# v2.net
KiCad netlist of a schematic drawn in Altium Designer
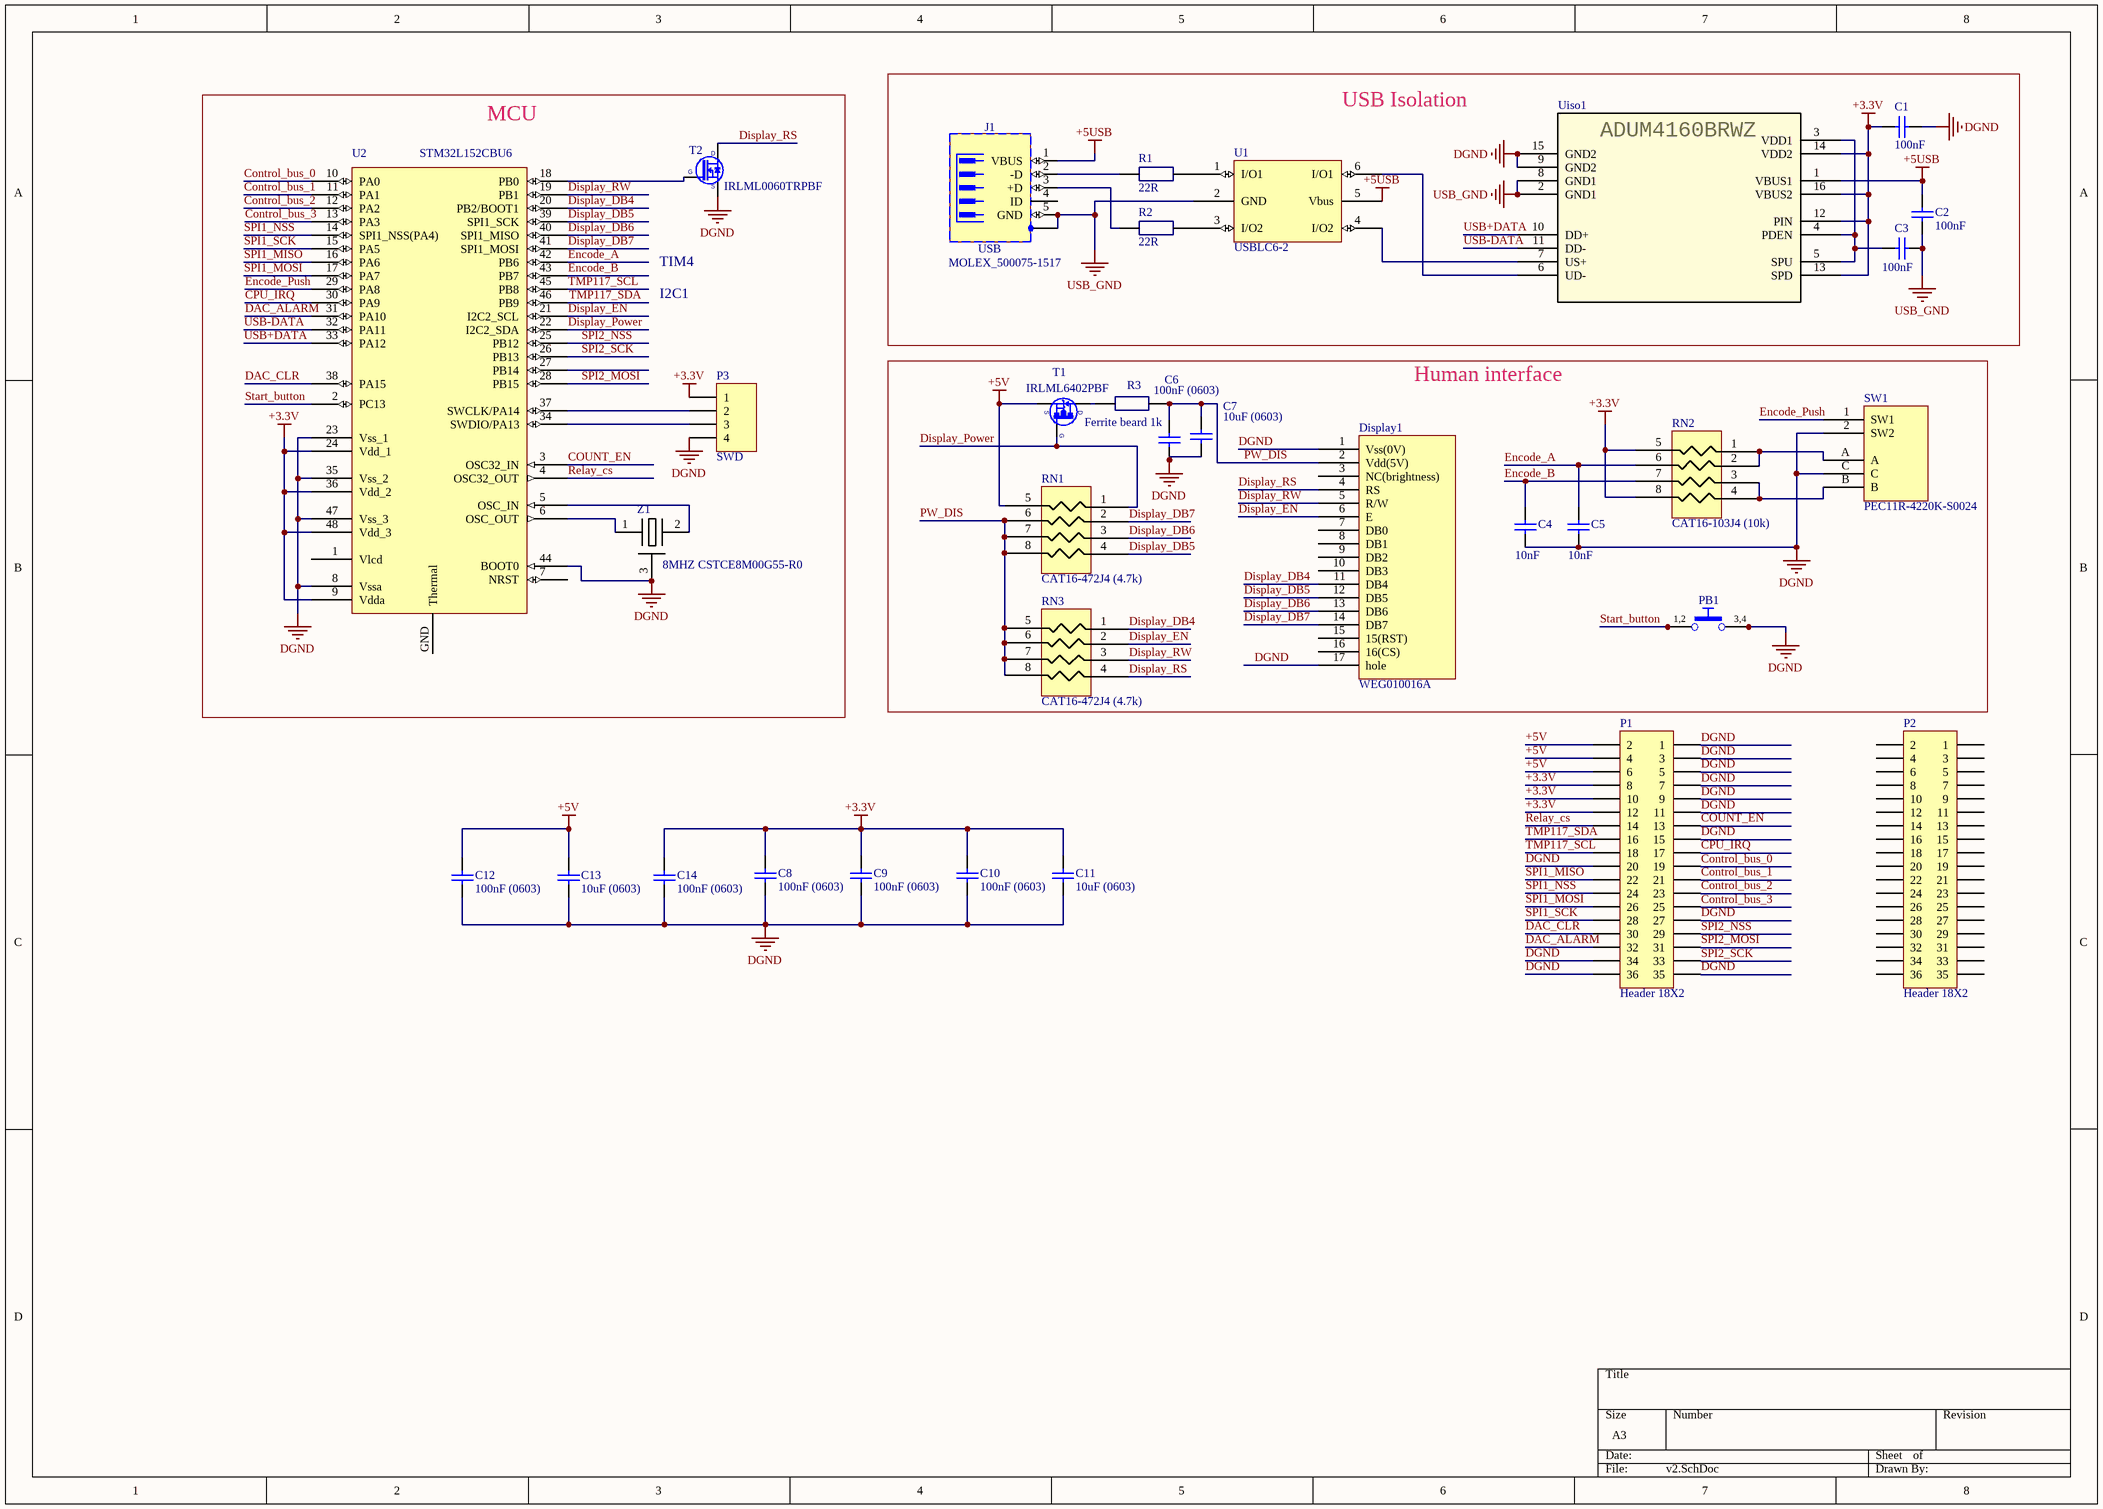
[diagram p0: v2.SchDoc]

(export (version "E")
  (design (tool "Eeschema 10.0.6"))
  (components
    (comp (ref "C1")
      (value "100nF")
      (footprint "CAP 0603")
      (description "Capacitor (Semiconductor SIM Model)")
      (fields (field (name "PUBLISHER") "Altium Limited"))
      (libsource (lib "Miscellaneous Devices") (part "Cap Semi"))
    )
    (comp (ref "C2")
      (value "100nF")
      (footprint "CAP 0603")
      (description "Capacitor (Semiconductor SIM Model)")
      (fields (field (name "PUBLISHER") "Altium Limited"))
      (libsource (lib "Miscellaneous Devices") (part "Cap Semi"))
    )
    (comp (ref "C3")
      (value "100nF")
      (footprint "CAP 0603")
      (description "Capacitor (Semiconductor SIM Model)")
      (fields (field (name "PUBLISHER") "Altium Limited"))
      (libsource (lib "Miscellaneous Devices") (part "Cap Semi"))
    )
    (comp (ref "C4")
      (value "10nF")
      (footprint "CAP 0603")
      (description "Capacitor (Semiconductor SIM Model)")
      (fields (field (name "PUBLISHER") "Altium Limited"))
      (libsource (lib "Miscellaneous Devices") (part "Cap Semi"))
    )
    (comp (ref "C5")
      (value "10nF")
      (footprint "CAP 0603")
      (description "Capacitor (Semiconductor SIM Model)")
      (fields (field (name "PUBLISHER") "Altium Limited"))
      (libsource (lib "Miscellaneous Devices") (part "Cap Semi"))
    )
    (comp (ref "C6")
      (value "100nF (0603)")
      (footprint "CAP 0603")
      (description "Capacitor (Semiconductor SIM Model)")
      (fields (field (name "PUBLISHER") "Altium Limited"))
      (libsource (lib "Miscellaneous Devices") (part "Cap Semi"))
    )
    (comp (ref "C7")
      (value "10uF (0603)")
      (footprint "CAP 0603")
      (description "Capacitor (Semiconductor SIM Model)")
      (fields (field (name "PUBLISHER") "Altium Limited"))
      (libsource (lib "Miscellaneous Devices") (part "Cap Semi"))
    )
    (comp (ref "C8")
      (value "100nF (0603)")
      (footprint "CAP 0603")
      (description "Capacitor (Semiconductor SIM Model)")
      (fields (field (name "PUBLISHER") "Altium Limited"))
      (libsource (lib "Miscellaneous Devices") (part "Cap Semi"))
    )
    (comp (ref "C9")
      (value "100nF (0603)")
      (footprint "CAP 0603")
      (description "Capacitor (Semiconductor SIM Model)")
      (fields (field (name "PUBLISHER") "Altium Limited"))
      (libsource (lib "Miscellaneous Devices") (part "Cap Semi"))
    )
    (comp (ref "C10")
      (value "100nF (0603)")
      (footprint "CAP 0603")
      (description "Capacitor (Semiconductor SIM Model)")
      (fields (field (name "PUBLISHER") "Altium Limited"))
      (libsource (lib "Miscellaneous Devices") (part "Cap Semi"))
    )
    (comp (ref "C11")
      (value "10uF (0603)")
      (footprint "CAP 0603")
      (description "Capacitor (Semiconductor SIM Model)")
      (fields (field (name "PUBLISHER") "Altium Limited"))
      (libsource (lib "Miscellaneous Devices") (part "Cap Semi"))
    )
    (comp (ref "C12")
      (value "100nF (0603)")
      (footprint "CAP 0603")
      (description "Capacitor (Semiconductor SIM Model)")
      (fields (field (name "PUBLISHER") "Altium Limited"))
      (libsource (lib "Miscellaneous Devices") (part "Cap Semi"))
    )
    (comp (ref "C13")
      (value "10uF (0603)")
      (footprint "CAP 0603")
      (description "Capacitor (Semiconductor SIM Model)")
      (fields (field (name "PUBLISHER") "Altium Limited"))
      (libsource (lib "Miscellaneous Devices") (part "Cap Semi"))
    )
    (comp (ref "C14")
      (value "100nF (0603)")
      (footprint "CAP 0603")
      (description "Capacitor (Semiconductor SIM Model)")
      (fields (field (name "PUBLISHER") "Altium Limited"))
      (libsource (lib "Miscellaneous Devices") (part "Cap Semi"))
    )
    (comp (ref "Display1")
      (value "WEG010016A")
      (footprint "WEG010016A")
      (libsource (lib "My SCH library") (part "WEG010016A"))
    )
    (comp (ref "J1")
      (value "USB")
      (footprint "MOLEX_500075-1517")
      (description "5 Pin + 1 Shield USB Receptacle")
      (fields
        (field (name "PART NUMBER") "MOLEX_500075-1517")
        (field (name "MANUFACTURER") "MOLEX")
        (field (name "MANUFACTURER PART NUMBER") "500075-1517")
        (field (name "AUTHOR") "CERN DEM JLC")
      )
      (libsource (lib "Connectors") (part "Connector USB 5 Pin + 1Shield"))
    )
    (comp (ref "P1")
      (value "Header 18X2")
      (footprint "HDR2X18")
      (description "Header, 18-Pin, Dual row")
      (fields (field (name "PUBLISHER") "Altium Limited"))
      (libsource (lib "Miscellaneous Connectors") (part "Header 18X2"))
    )
    (comp (ref "P2")
      (value "Header 18X2")
      (footprint "HDR2X18")
      (description "Header, 18-Pin, Dual row")
      (fields (field (name "PUBLISHER") "Altium Limited"))
      (libsource (lib "Miscellaneous Connectors") (part "Header 18X2"))
    )
    (comp (ref "P3")
      (value "SWD")
      (footprint "HDR1X4")
      (description "Header, 4-Pin")
      (fields (field (name "PUBLISHER") "Altium Limited"))
      (libsource (lib "Miscellaneous Connectors") (part "Header 4"))
    )
    (comp (ref "PB1")
      (value "Push Button")
      (footprint "PB_OMRON_B3F-1070")
      (description "Push-Button Switch SPDT")
      (fields
        (field (name "PART NUMBER") "PB_OMRON_B3F-1070")
        (field (name "MANUFACTURER") "OMRON")
        (field (name "AUTHOR") "CERN DEM JLC")
      )
      (libsource (lib "Eletro-mechanical") (part "PB SPST 12NO-34NO"))
    )
    (comp (ref "R1")
      (value "22R")
      (footprint "1608[0603]")
      (libsource (lib "Микрон-3") (part "Resistor 0805"))
    )
    (comp (ref "R2")
      (value "22R")
      (footprint "1608[0603]")
      (libsource (lib "Микрон-3") (part "Resistor 0805"))
    )
    (comp (ref "R3")
      (value "Ferrite beard 1k")
      (footprint "C1206")
      (libsource (lib "Микрон-3") (part "Resistor 0805"))
    )
    (comp (ref "RN1")
      (value "CAT16-472J4 (4.7k)")
      (footprint "CAT16-470J4LF")
      (libsource (lib "My SCH library") (part "CAT16-470J4LF"))
    )
    (comp (ref "RN2")
      (value "CAT16-103J4 (10k)")
      (footprint "CAT16-470J4LF")
      (libsource (lib "My SCH library") (part "CAT16-470J4LF"))
    )
    (comp (ref "RN3")
      (value "CAT16-472J4 (4.7k)")
      (footprint "CAT16-470J4LF")
      (libsource (lib "My SCH library") (part "CAT16-470J4LF"))
    )
    (comp (ref "SW1")
      (value "PEC11R-4220K-S0024")
      (footprint "PEC11R-4220K-S0024")
      (libsource (lib "My SCH library") (part "PEC11R-4220K-S0024"))
    )
    (comp (ref "T1")
      (value "IRLML6402PBF")
      (footprint "SOT95P237X112-3N")
      (description "P-CHANNEL MOSFET WITH ZENER DIODE")
      (fields (field (name "MANUFACTURER") "INTERNATIONAL RECTIFIER") (field (name "AUTHOR") "CERN DEM JLC"))
      (libsource (lib "ICs And Semiconductors") (part "P-MOSFET-DZ 1G 2S 3D"))
    )
    (comp (ref "T2")
      (value "IRLML0060TRPBF")
      (footprint "SOT95P237X112-3N")
      (description "N-CHANNEL MOSFET WITH DIODE")
      (fields (field (name "MANUFACTURER") "INTERNATIONAL RECTIFIER") (field (name "AUTHOR") "CERN DEM JLC"))
      (libsource (lib "ICs And Semiconductors") (part "N-MOSFET-D 1G 2S 3D"))
    )
    (comp (ref "U1") (value "USBLC6-2") (footprint "SOT23-6L") (libsource (lib "Микрон-3") (part "USBLC6-2")))
    (comp (ref "U2")
      (value "STM32L152CBU6")
      (footprint "UFQFPN48")
      (libsource (lib "My SCH library") (part "STM32L152CBU6"))
    )
    (comp (ref "Uiso1")
      (value "~")
      (footprint "RW_16_ADI")
      (description "No Description Available")
      (fields
        (field (name "MANUFACTURER_PART_NUMBER") "ADUM4160BRWZ")
        (field (name "COPYRIGHT") "Copyright (C) 2018 Accelerated Designs. All rights reserved")
      )
      (libsource (lib "Ramp-generator") (part "ADUM4160BRWZ"))
    )
    (comp (ref "Z1")
      (value "8MHZ CSTCE8M00G55-R0")
      (footprint "PRQV8.00CR5010Y000")
      (libsource (lib "My SCH library") (part "8MHZ_cap"))
    )
  )
  (nets
    (net (code "1") (name "+3.3V") (class "Default")
      (node (ref "C1") (pin "2") (pinfunction "2_2") (pintype "passive"))
      (node (ref "C10") (pin "1") (pinfunction "1_1") (pintype "passive"))
      (node (ref "C11") (pin "1") (pinfunction "1_1") (pintype "passive"))
      (node (ref "C14") (pin "1") (pinfunction "1_1") (pintype "passive"))
      (node (ref "C8") (pin "1") (pinfunction "1_1") (pintype "passive"))
      (node (ref "C9") (pin "1") (pinfunction "1_1") (pintype "passive"))
      (node (ref "P1") (pin "10") (pinfunction "10_10") (pintype "passive"))
      (node (ref "P1") (pin "12") (pinfunction "12_12") (pintype "passive"))
      (node (ref "P1") (pin "8") (pinfunction "8_8") (pintype "passive"))
      (node (ref "P3") (pin "1") (pinfunction "1_1") (pintype "passive"))
      (node (ref "RN2") (pin "5") (pinfunction "5_5") (pintype "passive"))
      (node (ref "RN2") (pin "8") (pinfunction "8_8") (pintype "passive"))
      (node (ref "U2") (pin "24") (pinfunction "Vdd_1_24") (pintype "power_in"))
      (node (ref "U2") (pin "36") (pinfunction "Vdd_2_36") (pintype "power_in"))
      (node (ref "U2") (pin "48") (pinfunction "Vdd_3_48") (pintype "power_in"))
      (node (ref "U2") (pin "9") (pinfunction "Vdda_9") (pintype "power_in"))
      (node (ref "Uiso1") (pin "12") (pinfunction "PIN_12") (pintype "passive"))
      (node (ref "Uiso1") (pin "13") (pinfunction "SPD_13") (pintype "passive"))
      (node (ref "Uiso1") (pin "14") (pinfunction "VDD2_14") (pintype "passive"))
      (node (ref "Uiso1") (pin "16") (pinfunction "VBUS2_16") (pintype "passive"))
    )
    (net (code "2") (name "+5USB") (class "Default")
      (node (ref "C2") (pin "2") (pinfunction "2_2") (pintype "passive"))
      (node (ref "J1") (pin "1") (pinfunction "VBUS_1") (pintype "bidirectional"))
      (node (ref "U1") (pin "5") (pinfunction "Vbus_5") (pintype "power_in"))
      (node (ref "Uiso1") (pin "1") (pinfunction "VBUS1_1") (pintype "passive"))
    )
    (net (code "3") (name "+5V") (class "Default")
      (node (ref "C12") (pin "1") (pinfunction "1_1") (pintype "passive"))
      (node (ref "C13") (pin "1") (pinfunction "1_1") (pintype "passive"))
      (node (ref "P1") (pin "2") (pinfunction "2_2") (pintype "passive"))
      (node (ref "P1") (pin "4") (pinfunction "4_4") (pintype "passive"))
      (node (ref "P1") (pin "6") (pinfunction "6_6") (pintype "passive"))
      (node (ref "RN1") (pin "5") (pinfunction "5_5") (pintype "passive"))
      (node (ref "T1") (pin "2") (pinfunction "S_2") (pintype "passive"))
    )
    (net (code "4") (name "/COUNT_EN") (class "Default")
      (node (ref "P1") (pin "13") (pinfunction "13_13") (pintype "passive"))
      (node (ref "U2") (pin "3") (pinfunction "OSC32_IN_3") (pintype "input"))
    )
    (net (code "5") (name "/CPU_IRQ") (class "Default")
      (node (ref "P1") (pin "17") (pinfunction "17_17") (pintype "passive"))
      (node (ref "U2") (pin "30") (pinfunction "PA9_30") (pintype "bidirectional"))
    )
    (net (code "6") (name "/Control_bus_0") (class "Default")
      (node (ref "P1") (pin "19") (pinfunction "19_19") (pintype "passive"))
      (node (ref "U2") (pin "10") (pinfunction "PA0_10") (pintype "bidirectional"))
    )
    (net (code "7") (name "/Control_bus_1") (class "Default")
      (node (ref "P1") (pin "21") (pinfunction "21_21") (pintype "passive"))
      (node (ref "U2") (pin "11") (pinfunction "PA1_11") (pintype "bidirectional"))
    )
    (net (code "8") (name "/Control_bus_2") (class "Default")
      (node (ref "P1") (pin "23") (pinfunction "23_23") (pintype "passive"))
      (node (ref "U2") (pin "12") (pinfunction "PA2_12") (pintype "bidirectional"))
    )
    (net (code "9") (name "/Control_bus_3") (class "Default")
      (node (ref "P1") (pin "25") (pinfunction "25_25") (pintype "passive"))
      (node (ref "U2") (pin "13") (pinfunction "PA3_13") (pintype "bidirectional"))
    )
    (net (code "10") (name "/DAC_ALARM") (class "Default")
      (node (ref "P1") (pin "32") (pinfunction "32_32") (pintype "passive"))
      (node (ref "U2") (pin "31") (pinfunction "PA10_31") (pintype "bidirectional"))
    )
    (net (code "11") (name "/DAC_CLR") (class "Default")
      (node (ref "P1") (pin "30") (pinfunction "30_30") (pintype "passive"))
      (node (ref "U2") (pin "38") (pinfunction "PA15_38") (pintype "bidirectional"))
    )
    (net (code "12") (name "/Display_DB4") (class "Default")
      (node (ref "Display1") (pin "11") (pinfunction "DB4_11") (pintype "passive"))
      (node (ref "RN3") (pin "1") (pinfunction "1_1") (pintype "passive"))
      (node (ref "U2") (pin "20") (pinfunction "PB2/BOOT1_20") (pintype "bidirectional"))
    )
    (net (code "13") (name "/Display_DB5") (class "Default")
      (node (ref "Display1") (pin "12") (pinfunction "DB5_12") (pintype "passive"))
      (node (ref "RN1") (pin "4") (pinfunction "4_4") (pintype "passive"))
      (node (ref "U2") (pin "39") (pinfunction "SPI1_SCK_39") (pintype "bidirectional"))
    )
    (net (code "14") (name "/Display_DB6") (class "Default")
      (node (ref "Display1") (pin "13") (pinfunction "DB6_13") (pintype "passive"))
      (node (ref "RN1") (pin "3") (pinfunction "3_3") (pintype "passive"))
      (node (ref "U2") (pin "40") (pinfunction "SPI1_MISO_40") (pintype "bidirectional"))
    )
    (net (code "15") (name "/Display_DB7") (class "Default")
      (node (ref "Display1") (pin "14") (pinfunction "DB7_14") (pintype "passive"))
      (node (ref "RN1") (pin "2") (pinfunction "2_2") (pintype "passive"))
      (node (ref "U2") (pin "41") (pinfunction "SPI1_MOSI_41") (pintype "bidirectional"))
    )
    (net (code "16") (name "/Display_EN") (class "Default")
      (node (ref "Display1") (pin "6") (pinfunction "E_6") (pintype "passive"))
      (node (ref "RN3") (pin "2") (pinfunction "2_2") (pintype "passive"))
      (node (ref "U2") (pin "21") (pinfunction "I2C2_SCL_21") (pintype "bidirectional"))
    )
    (net (code "17") (name "/Display_Power") (class "Default")
      (node (ref "RN1") (pin "1") (pinfunction "1_1") (pintype "passive"))
      (node (ref "T1") (pin "1") (pinfunction "G_1") (pintype "passive"))
      (node (ref "U2") (pin "22") (pinfunction "I2C2_SDA_22") (pintype "bidirectional"))
    )
    (net (code "18") (name "/Display_RS") (class "Default")
      (node (ref "Display1") (pin "4") (pinfunction "RS_4") (pintype "passive"))
      (node (ref "RN3") (pin "4") (pinfunction "4_4") (pintype "passive"))
      (node (ref "T2") (pin "3") (pinfunction "D_3") (pintype "passive"))
    )
    (net (code "19") (name "/Display_RW") (class "Default")
      (node (ref "Display1") (pin "5") (pinfunction "R/W_5") (pintype "passive"))
      (node (ref "RN3") (pin "3") (pinfunction "3_3") (pintype "passive"))
      (node (ref "U2") (pin "19") (pinfunction "PB1_19") (pintype "bidirectional"))
    )
    (net (code "20") (name "/Encode_A") (class "Default")
      (node (ref "C5") (pin "1") (pinfunction "1_1") (pintype "passive"))
      (node (ref "RN2") (pin "6") (pinfunction "6_6") (pintype "passive"))
      (node (ref "U2") (pin "42") (pinfunction "PB6_42") (pintype "bidirectional"))
    )
    (net (code "21") (name "/Encode_B") (class "Default")
      (node (ref "C4") (pin "1") (pinfunction "1_1") (pintype "passive"))
      (node (ref "RN2") (pin "7") (pinfunction "7_7") (pintype "passive"))
      (node (ref "U2") (pin "43") (pinfunction "PB7_43") (pintype "bidirectional"))
    )
    (net (code "22") (name "/Encode_Push") (class "Default")
      (node (ref "SW1") (pin "1") (pinfunction "SW1_1") (pintype "open_collector"))
      (node (ref "U2") (pin "29") (pinfunction "PA8_29") (pintype "bidirectional"))
    )
    (net (code "23") (name "/PW_DIS") (class "Default")
      (node (ref "C6") (pin "1") (pinfunction "1_1") (pintype "passive"))
      (node (ref "C7") (pin "1") (pinfunction "1_1") (pintype "passive"))
      (node (ref "Display1") (pin "2") (pinfunction "Vdd(5V)_2") (pintype "passive"))
      (node (ref "R3") (pin "1") (pinfunction "A_1") (pintype "passive"))
      (node (ref "RN1") (pin "6") (pinfunction "6_6") (pintype "passive"))
      (node (ref "RN1") (pin "7") (pinfunction "7_7") (pintype "passive"))
      (node (ref "RN1") (pin "8") (pinfunction "8_8") (pintype "passive"))
      (node (ref "RN3") (pin "5") (pinfunction "5_5") (pintype "passive"))
      (node (ref "RN3") (pin "6") (pinfunction "6_6") (pintype "passive"))
      (node (ref "RN3") (pin "7") (pinfunction "7_7") (pintype "passive"))
      (node (ref "RN3") (pin "8") (pinfunction "8_8") (pintype "passive"))
    )
    (net (code "24") (name "/Relay_cs") (class "Default")
      (node (ref "P1") (pin "14") (pinfunction "14_14") (pintype "passive"))
      (node (ref "U2") (pin "4") (pinfunction "OSC32_OUT_4") (pintype "output"))
    )
    (net (code "25") (name "/SPI1_MISO") (class "Default")
      (node (ref "P1") (pin "22") (pinfunction "22_22") (pintype "passive"))
      (node (ref "U2") (pin "16") (pinfunction "PA6_16") (pintype "bidirectional"))
    )
    (net (code "26") (name "/SPI1_MOSI") (class "Default")
      (node (ref "P1") (pin "26") (pinfunction "26_26") (pintype "passive"))
      (node (ref "U2") (pin "17") (pinfunction "PA7_17") (pintype "bidirectional"))
    )
    (net (code "27") (name "/SPI1_NSS") (class "Default")
      (node (ref "P1") (pin "24") (pinfunction "24_24") (pintype "passive"))
      (node (ref "U2") (pin "14") (pinfunction "SPI1_NSS(PA4)_14") (pintype "bidirectional"))
    )
    (net (code "28") (name "/SPI1_SCK") (class "Default")
      (node (ref "P1") (pin "28") (pinfunction "28_28") (pintype "passive"))
      (node (ref "U2") (pin "15") (pinfunction "PA5_15") (pintype "bidirectional"))
    )
    (net (code "29") (name "/SPI2_MOSI") (class "Default")
      (node (ref "P1") (pin "31") (pinfunction "31_31") (pintype "passive"))
      (node (ref "U2") (pin "28") (pinfunction "PB15_28") (pintype "bidirectional"))
    )
    (net (code "30") (name "/SPI2_NSS") (class "Default")
      (node (ref "P1") (pin "29") (pinfunction "29_29") (pintype "passive"))
      (node (ref "U2") (pin "25") (pinfunction "PB12_25") (pintype "bidirectional"))
    )
    (net (code "31") (name "/SPI2_SCK") (class "Default")
      (node (ref "P1") (pin "33") (pinfunction "33_33") (pintype "passive"))
      (node (ref "U2") (pin "26") (pinfunction "PB13_26") (pintype "bidirectional"))
    )
    (net (code "32") (name "/Start_button") (class "Default")
      (node (ref "PB1") (pin "1") (pinfunction "1_1") (pintype "passive"))
      (node (ref "PB1") (pin "2") (pinfunction "2_2") (pintype "passive"))
      (node (ref "U2") (pin "2") (pinfunction "PC13_2") (pintype "bidirectional"))
    )
    (net (code "33") (name "/TMP117_SCL") (class "Default")
      (node (ref "P1") (pin "18") (pinfunction "18_18") (pintype "passive"))
      (node (ref "U2") (pin "45") (pinfunction "PB8_45") (pintype "bidirectional"))
    )
    (net (code "34") (name "/TMP117_SDA") (class "Default")
      (node (ref "P1") (pin "16") (pinfunction "16_16") (pintype "passive"))
      (node (ref "U2") (pin "46") (pinfunction "PB9_46") (pintype "bidirectional"))
    )
    (net (code "35") (name "/USB+DATA") (class "Default")
      (node (ref "U2") (pin "33") (pinfunction "PA12_33") (pintype "bidirectional"))
      (node (ref "Uiso1") (pin "10") (pinfunction "DD+_10") (pintype "passive"))
    )
    (net (code "36") (name "/USB-DATA") (class "Default")
      (node (ref "U2") (pin "32") (pinfunction "PA11_32") (pintype "bidirectional"))
      (node (ref "Uiso1") (pin "11") (pinfunction "DD-_11") (pintype "passive"))
    )
    (net (code "37") (name "DGND") (class "Default")
      (node (ref "C1") (pin "1") (pinfunction "1_1") (pintype "passive"))
      (node (ref "C10") (pin "2") (pinfunction "2_2") (pintype "passive"))
      (node (ref "C11") (pin "2") (pinfunction "2_2") (pintype "passive"))
      (node (ref "C12") (pin "2") (pinfunction "2_2") (pintype "passive"))
      (node (ref "C13") (pin "2") (pinfunction "2_2") (pintype "passive"))
      (node (ref "C14") (pin "2") (pinfunction "2_2") (pintype "passive"))
      (node (ref "C4") (pin "2") (pinfunction "2_2") (pintype "passive"))
      (node (ref "C5") (pin "2") (pinfunction "2_2") (pintype "passive"))
      (node (ref "C6") (pin "2") (pinfunction "2_2") (pintype "passive"))
      (node (ref "C7") (pin "2") (pinfunction "2_2") (pintype "passive"))
      (node (ref "C8") (pin "2") (pinfunction "2_2") (pintype "passive"))
      (node (ref "C9") (pin "2") (pinfunction "2_2") (pintype "passive"))
      (node (ref "Display1") (pin "1") (pinfunction "Vss(0V)_1") (pintype "passive"))
      (node (ref "Display1") (pin "17") (pinfunction "hole_17") (pintype "passive"))
      (node (ref "P1") (pin "1") (pinfunction "1_1") (pintype "passive"))
      (node (ref "P1") (pin "11") (pinfunction "11_11") (pintype "passive"))
      (node (ref "P1") (pin "15") (pinfunction "15_15") (pintype "passive"))
      (node (ref "P1") (pin "20") (pinfunction "20_20") (pintype "passive"))
      (node (ref "P1") (pin "27") (pinfunction "27_27") (pintype "passive"))
      (node (ref "P1") (pin "3") (pinfunction "3_3") (pintype "passive"))
      (node (ref "P1") (pin "34") (pinfunction "34_34") (pintype "passive"))
      (node (ref "P1") (pin "35") (pinfunction "35_35") (pintype "passive"))
      (node (ref "P1") (pin "36") (pinfunction "36_36") (pintype "passive"))
      (node (ref "P1") (pin "5") (pinfunction "5_5") (pintype "passive"))
      (node (ref "P1") (pin "7") (pinfunction "7_7") (pintype "passive"))
      (node (ref "P1") (pin "9") (pinfunction "9_9") (pintype "passive"))
      (node (ref "P3") (pin "4") (pinfunction "4_4") (pintype "passive"))
      (node (ref "PB1") (pin "3") (pinfunction "3_3") (pintype "passive"))
      (node (ref "PB1") (pin "4") (pinfunction "4_4") (pintype "passive"))
      (node (ref "SW1") (pin "2") (pinfunction "SW2_2") (pintype "open_collector"))
      (node (ref "SW1") (pin "C") (pinfunction "C_C") (pintype "open_collector"))
      (node (ref "T2") (pin "2") (pinfunction "S_2") (pintype "passive"))
      (node (ref "U2") (pin "23") (pinfunction "Vss_1_23") (pintype "power_in"))
      (node (ref "U2") (pin "35") (pinfunction "Vss_2_35") (pintype "power_in"))
      (node (ref "U2") (pin "44") (pinfunction "BOOT0_44") (pintype "input"))
      (node (ref "U2") (pin "47") (pinfunction "Vss_3_47") (pintype "power_in"))
      (node (ref "U2") (pin "8") (pinfunction "Vssa_8") (pintype "power_in"))
      (node (ref "Uiso1") (pin "15") (pinfunction "GND2_15") (pintype "passive"))
      (node (ref "Uiso1") (pin "9") (pinfunction "GND2_9") (pintype "passive"))
      (node (ref "Z1") (pin "3") (pinfunction "50_3") (pintype "passive"))
    )
    (net (code "38") (name "Net-(J1-+D)") (class "Default")
      (node (ref "J1") (pin "3") (pinfunction "+D_3") (pintype "bidirectional"))
      (node (ref "R2") (pin "2") (pinfunction "2_2") (pintype "passive"))
    )
    (net (code "39") (name "Net-(J1--D)") (class "Default")
      (node (ref "J1") (pin "2") (pinfunction "-D_2") (pintype "bidirectional"))
      (node (ref "R1") (pin "2") (pinfunction "2_2") (pintype "passive"))
    )
    (net (code "40") (name "Net-(R1-A)") (class "Default")
      (node (ref "R1") (pin "1") (pinfunction "A_1") (pintype "passive"))
      (node (ref "U1") (pin "1") (pinfunction "I/O1_1") (pintype "bidirectional"))
    )
    (net (code "41") (name "Net-(R2-A)") (class "Default")
      (node (ref "R2") (pin "1") (pinfunction "A_1") (pintype "passive"))
      (node (ref "U1") (pin "3") (pinfunction "I/O2_3") (pintype "bidirectional"))
    )
    (net (code "42") (name "Net-(RN2-Pad1)") (class "Default")
      (node (ref "RN2") (pin "1") (pinfunction "1_1") (pintype "passive"))
      (node (ref "RN2") (pin "2") (pinfunction "2_2") (pintype "passive"))
      (node (ref "SW1") (pin "A") (pinfunction "A_A") (pintype "open_collector"))
    )
    (net (code "43") (name "Net-(RN2-Pad3)") (class "Default")
      (node (ref "RN2") (pin "3") (pinfunction "3_3") (pintype "passive"))
      (node (ref "RN2") (pin "4") (pinfunction "4_4") (pintype "passive"))
      (node (ref "SW1") (pin "B") (pinfunction "B_B") (pintype "open_collector"))
    )
    (net (code "44") (name "Net-(T1-D)") (class "Default")
      (node (ref "R3") (pin "2") (pinfunction "2_2") (pintype "passive"))
      (node (ref "T1") (pin "3") (pinfunction "D_3") (pintype "passive"))
    )
    (net (code "45") (name "Net-(T2-G)") (class "Default")
      (node (ref "T2") (pin "1") (pinfunction "G_1") (pintype "passive"))
      (node (ref "U2") (pin "18") (pinfunction "PB0_18") (pintype "bidirectional"))
    )
    (net (code "46") (name "Net-(U2-OSC_IN)") (class "Default")
      (node (ref "U2") (pin "5") (pinfunction "OSC_IN_5") (pintype "input"))
      (node (ref "Z1") (pin "2") (pinfunction "2_2") (pintype "passive"))
    )
    (net (code "47") (name "Net-(U2-OSC_OUT)") (class "Default")
      (node (ref "U2") (pin "6") (pinfunction "OSC_OUT_6") (pintype "output"))
      (node (ref "Z1") (pin "1") (pinfunction "50_1") (pintype "passive"))
    )
    (net (code "48") (name "Net-(U2-SWCLK{slash}PA14)") (class "Default")
      (node (ref "P3") (pin "2") (pinfunction "2_2") (pintype "passive"))
      (node (ref "U2") (pin "37") (pinfunction "SWCLK/PA14_37") (pintype "bidirectional"))
    )
    (net (code "49") (name "Net-(U2-SWDIO{slash}PA13)") (class "Default")
      (node (ref "P3") (pin "3") (pinfunction "3_3") (pintype "passive"))
      (node (ref "U2") (pin "34") (pinfunction "SWDIO/PA13_34") (pintype "bidirectional"))
    )
    (net (code "50") (name "Net-(Uiso1-PDEN)") (class "Default")
      (node (ref "C3") (pin "2") (pinfunction "2_2") (pintype "passive"))
      (node (ref "Uiso1") (pin "3") (pinfunction "VDD1_3") (pintype "passive"))
      (node (ref "Uiso1") (pin "4") (pinfunction "PDEN_4") (pintype "passive"))
      (node (ref "Uiso1") (pin "5") (pinfunction "SPU_5") (pintype "passive"))
    )
    (net (code "51") (name "Net-(Uiso1-UD-)") (class "Default")
      (node (ref "U1") (pin "6") (pinfunction "I/O1_6") (pintype "bidirectional"))
      (node (ref "Uiso1") (pin "6") (pinfunction "UD-_6") (pintype "passive"))
    )
    (net (code "52") (name "Net-(Uiso1-US+)") (class "Default")
      (node (ref "U1") (pin "4") (pinfunction "I/O2_4") (pintype "bidirectional"))
      (node (ref "Uiso1") (pin "7") (pinfunction "US+_7") (pintype "passive"))
    )
    (net (code "53") (name "USB_GND") (class "Default")
      (node (ref "C2") (pin "1") (pinfunction "1_1") (pintype "passive"))
      (node (ref "C3") (pin "1") (pinfunction "1_1") (pintype "passive"))
      (node (ref "J1") (pin "5") (pinfunction "GND_5") (pintype "bidirectional"))
      (node (ref "J1") (pin "6") (pinfunction "SH_6") (pintype "power_in"))
      (node (ref "U1") (pin "2") (pinfunction "GND_2") (pintype "power_in"))
      (node (ref "Uiso1") (pin "2") (pinfunction "GND1_2") (pintype "passive"))
      (node (ref "Uiso1") (pin "8") (pinfunction "GND1_8") (pintype "passive"))
    )
    (net (code "54") (name "unconnected-(Display1-15(RST)-Pad15)") (class "Default")
      (node (ref "Display1") (pin "15") (pinfunction "15(RST)_15") (pintype "passive"))
    )
    (net (code "55") (name "unconnected-(Display1-16(CS)-Pad16)") (class "Default")
      (node (ref "Display1") (pin "16") (pinfunction "16(CS)_16") (pintype "passive"))
    )
    (net (code "56") (name "unconnected-(Display1-DB0-Pad7)") (class "Default")
      (node (ref "Display1") (pin "7") (pinfunction "DB0_7") (pintype "passive"))
    )
    (net (code "57") (name "unconnected-(Display1-DB1-Pad8)") (class "Default")
      (node (ref "Display1") (pin "8") (pinfunction "DB1_8") (pintype "passive"))
    )
    (net (code "58") (name "unconnected-(Display1-DB2-Pad9)") (class "Default")
      (node (ref "Display1") (pin "9") (pinfunction "DB2_9") (pintype "passive"))
    )
    (net (code "59") (name "unconnected-(Display1-DB3-Pad10)") (class "Default")
      (node (ref "Display1") (pin "10") (pinfunction "DB3_10") (pintype "passive"))
    )
    (net (code "60") (name "unconnected-(Display1-NC(brightness)-Pad3)") (class "Default")
      (node (ref "Display1") (pin "3") (pinfunction "NC(brightness)_3") (pintype "passive"))
    )
    (net (code "61") (name "unconnected-(J1-ID-Pad4)") (class "Default")
      (node (ref "J1") (pin "4") (pinfunction "ID_4") (pintype "passive"))
    )
    (net (code "62") (name "unconnected-(P2-Pad1)") (class "Default")
      (node (ref "P2") (pin "1") (pinfunction "1_1") (pintype "passive"))
    )
    (net (code "63") (name "unconnected-(P2-Pad2)") (class "Default")
      (node (ref "P2") (pin "2") (pinfunction "2_2") (pintype "passive"))
    )
    (net (code "64") (name "unconnected-(P2-Pad3)") (class "Default")
      (node (ref "P2") (pin "3") (pinfunction "3_3") (pintype "passive"))
    )
    (net (code "65") (name "unconnected-(P2-Pad4)") (class "Default")
      (node (ref "P2") (pin "4") (pinfunction "4_4") (pintype "passive"))
    )
    (net (code "66") (name "unconnected-(P2-Pad5)") (class "Default")
      (node (ref "P2") (pin "5") (pinfunction "5_5") (pintype "passive"))
    )
    (net (code "67") (name "unconnected-(P2-Pad6)") (class "Default")
      (node (ref "P2") (pin "6") (pinfunction "6_6") (pintype "passive"))
    )
    (net (code "68") (name "unconnected-(P2-Pad7)") (class "Default")
      (node (ref "P2") (pin "7") (pinfunction "7_7") (pintype "passive"))
    )
    (net (code "69") (name "unconnected-(P2-Pad8)") (class "Default")
      (node (ref "P2") (pin "8") (pinfunction "8_8") (pintype "passive"))
    )
    (net (code "70") (name "unconnected-(P2-Pad9)") (class "Default")
      (node (ref "P2") (pin "9") (pinfunction "9_9") (pintype "passive"))
    )
    (net (code "71") (name "unconnected-(P2-Pad10)") (class "Default")
      (node (ref "P2") (pin "10") (pinfunction "10_10") (pintype "passive"))
    )
    (net (code "72") (name "unconnected-(P2-Pad11)") (class "Default")
      (node (ref "P2") (pin "11") (pinfunction "11_11") (pintype "passive"))
    )
    (net (code "73") (name "unconnected-(P2-Pad12)") (class "Default")
      (node (ref "P2") (pin "12") (pinfunction "12_12") (pintype "passive"))
    )
    (net (code "74") (name "unconnected-(P2-Pad13)") (class "Default")
      (node (ref "P2") (pin "13") (pinfunction "13_13") (pintype "passive"))
    )
    (net (code "75") (name "unconnected-(P2-Pad14)") (class "Default")
      (node (ref "P2") (pin "14") (pinfunction "14_14") (pintype "passive"))
    )
    (net (code "76") (name "unconnected-(P2-Pad15)") (class "Default")
      (node (ref "P2") (pin "15") (pinfunction "15_15") (pintype "passive"))
    )
    (net (code "77") (name "unconnected-(P2-Pad16)") (class "Default")
      (node (ref "P2") (pin "16") (pinfunction "16_16") (pintype "passive"))
    )
    (net (code "78") (name "unconnected-(P2-Pad17)") (class "Default")
      (node (ref "P2") (pin "17") (pinfunction "17_17") (pintype "passive"))
    )
    (net (code "79") (name "unconnected-(P2-Pad18)") (class "Default")
      (node (ref "P2") (pin "18") (pinfunction "18_18") (pintype "passive"))
    )
    (net (code "80") (name "unconnected-(P2-Pad19)") (class "Default")
      (node (ref "P2") (pin "19") (pinfunction "19_19") (pintype "passive"))
    )
    (net (code "81") (name "unconnected-(P2-Pad20)") (class "Default")
      (node (ref "P2") (pin "20") (pinfunction "20_20") (pintype "passive"))
    )
    (net (code "82") (name "unconnected-(P2-Pad21)") (class "Default")
      (node (ref "P2") (pin "21") (pinfunction "21_21") (pintype "passive"))
    )
    (net (code "83") (name "unconnected-(P2-Pad22)") (class "Default")
      (node (ref "P2") (pin "22") (pinfunction "22_22") (pintype "passive"))
    )
    (net (code "84") (name "unconnected-(P2-Pad23)") (class "Default")
      (node (ref "P2") (pin "23") (pinfunction "23_23") (pintype "passive"))
    )
    (net (code "85") (name "unconnected-(P2-Pad24)") (class "Default")
      (node (ref "P2") (pin "24") (pinfunction "24_24") (pintype "passive"))
    )
    (net (code "86") (name "unconnected-(P2-Pad25)") (class "Default")
      (node (ref "P2") (pin "25") (pinfunction "25_25") (pintype "passive"))
    )
    (net (code "87") (name "unconnected-(P2-Pad26)") (class "Default")
      (node (ref "P2") (pin "26") (pinfunction "26_26") (pintype "passive"))
    )
    (net (code "88") (name "unconnected-(P2-Pad27)") (class "Default")
      (node (ref "P2") (pin "27") (pinfunction "27_27") (pintype "passive"))
    )
    (net (code "89") (name "unconnected-(P2-Pad28)") (class "Default")
      (node (ref "P2") (pin "28") (pinfunction "28_28") (pintype "passive"))
    )
    (net (code "90") (name "unconnected-(P2-Pad29)") (class "Default")
      (node (ref "P2") (pin "29") (pinfunction "29_29") (pintype "passive"))
    )
    (net (code "91") (name "unconnected-(P2-Pad30)") (class "Default")
      (node (ref "P2") (pin "30") (pinfunction "30_30") (pintype "passive"))
    )
    (net (code "92") (name "unconnected-(P2-Pad31)") (class "Default")
      (node (ref "P2") (pin "31") (pinfunction "31_31") (pintype "passive"))
    )
    (net (code "93") (name "unconnected-(P2-Pad32)") (class "Default")
      (node (ref "P2") (pin "32") (pinfunction "32_32") (pintype "passive"))
    )
    (net (code "94") (name "unconnected-(P2-Pad33)") (class "Default")
      (node (ref "P2") (pin "33") (pinfunction "33_33") (pintype "passive"))
    )
    (net (code "95") (name "unconnected-(P2-Pad34)") (class "Default")
      (node (ref "P2") (pin "34") (pinfunction "34_34") (pintype "passive"))
    )
    (net (code "96") (name "unconnected-(P2-Pad35)") (class "Default")
      (node (ref "P2") (pin "35") (pinfunction "35_35") (pintype "passive"))
    )
    (net (code "97") (name "unconnected-(P2-Pad36)") (class "Default")
      (node (ref "P2") (pin "36") (pinfunction "36_36") (pintype "passive"))
    )
    (net (code "98") (name "unconnected-(U2-NRST-Pad7)") (class "Default")
      (node (ref "U2") (pin "7") (pinfunction "NRST_7") (pintype "bidirectional"))
    )
    (net (code "99") (name "unconnected-(U2-PB14-Pad27)") (class "Default")
      (node (ref "U2") (pin "27") (pinfunction "PB14_27") (pintype "bidirectional"))
    )
    (net (code "100") (name "unconnected-(U2-Thermal-PadGND)") (class "Default")
      (node (ref "U2") (pin "GND") (pinfunction "Thermal_GND") (pintype "power_in"))
    )
    (net (code "101") (name "unconnected-(U2-Vlcd-Pad1)") (class "Default")
      (node (ref "U2") (pin "1") (pinfunction "Vlcd_1") (pintype "power_in"))
    )
  )
)
